# SCH_lic-555_2025-01-28.net
KiCad netlist of a schematic drawn in EasyEDA
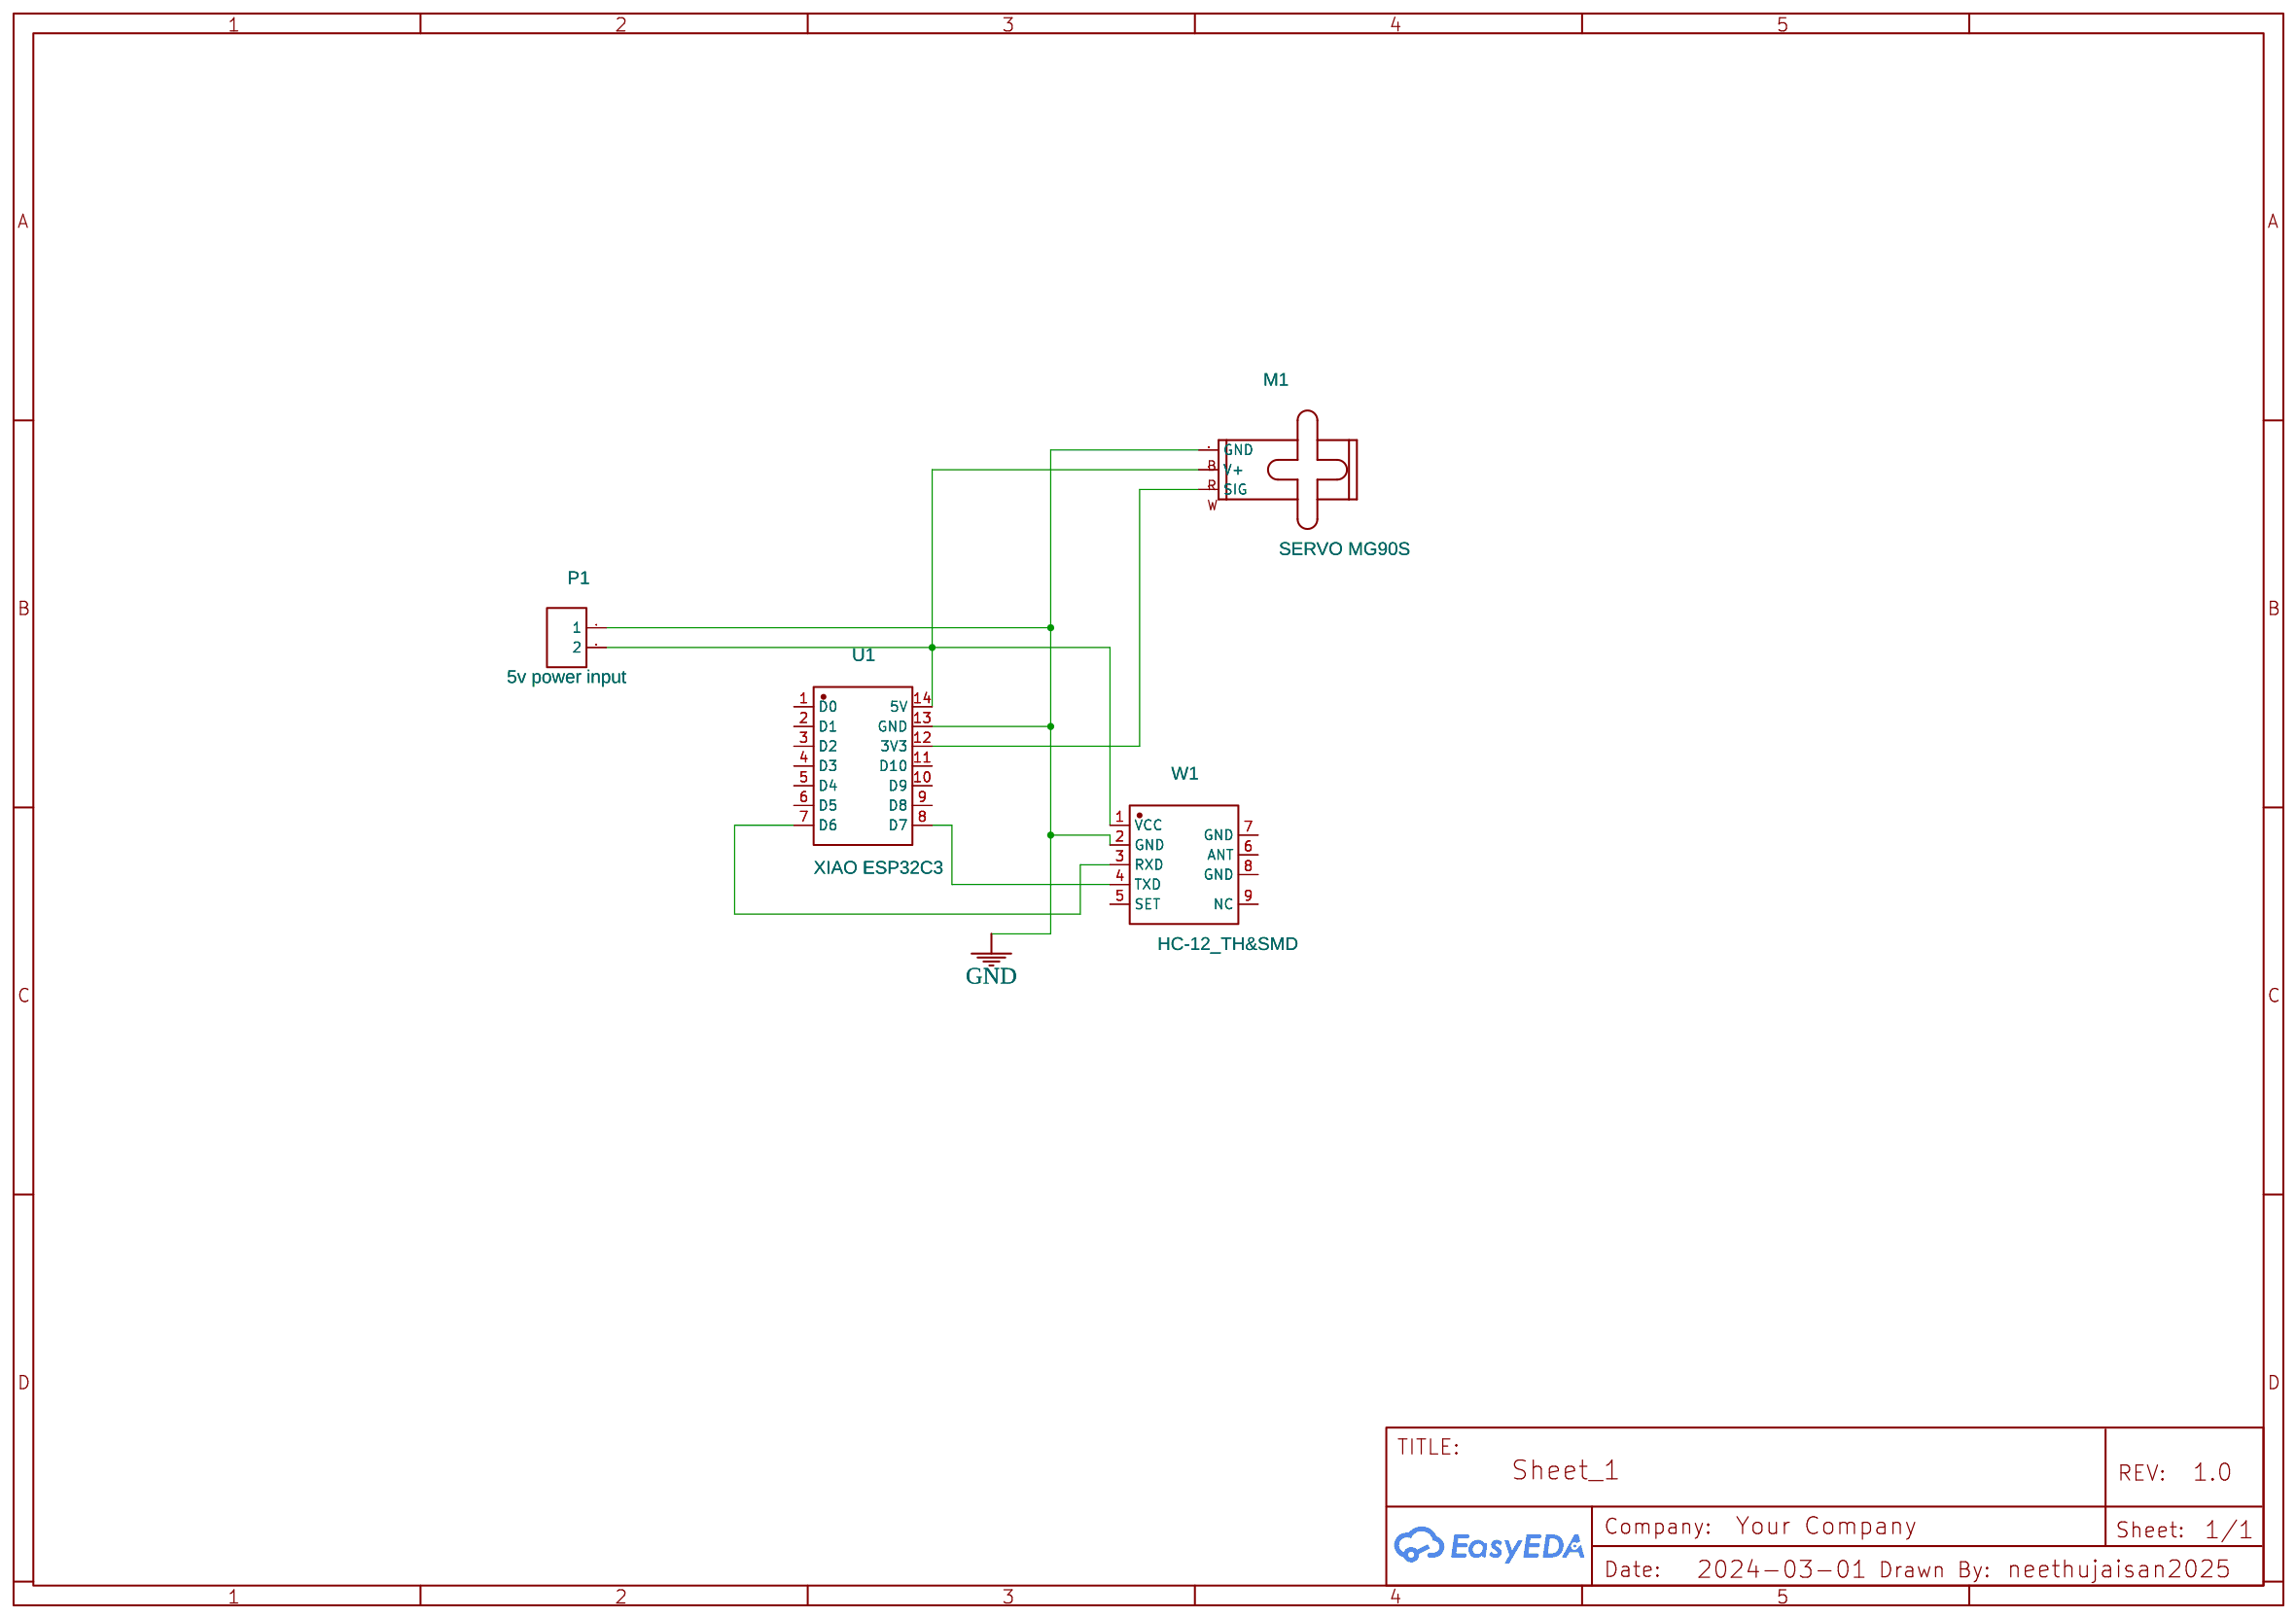
[diagram p0: schematic sheet]

(export (version "E")
  (design (tool "Eeschema 10.0.6"))
  (components
    (comp (ref "M1") (value "SERVO MG90S") (libsource (lib "") (part "SMALL_SERVO")))
    (comp (ref "P1") (value "5v power input") (libsource (lib "") (part "HDR-F-2.54_1x2")))
    (comp (ref "U1") (value "XIAO ESP32C3") (libsource (lib "") (part "XIAO ESP32C3")))
    (comp (ref "W1") (value "HC-12_TH&SMD") (libsource (lib "") (part "HC-12_TH&SMD")))
  )
  (nets
    (net (code "1") (name "GND") (class "Default")
      (node (ref "M1") (pin "3") (pinfunction "GND_3") (pintype "unspecified"))
      (node (ref "P1") (pin "1") (pinfunction "1_1") (pintype "input"))
      (node (ref "U1") (pin "13") (pinfunction "GND_13") (pintype "unspecified"))
      (node (ref "W1") (pin "2") (pinfunction "GND_2") (pintype "unspecified"))
    )
    (net (code "2") (name "Net-(M1-SIG)") (class "Default")
      (node (ref "M1") (pin "1") (pinfunction "SIG_1") (pintype "unspecified"))
      (node (ref "U1") (pin "12") (pinfunction "3V3_12") (pintype "unspecified"))
    )
    (net (code "3") (name "Net-(M1-V+)") (class "Default")
      (node (ref "M1") (pin "2") (pinfunction "V+_2") (pintype "unspecified"))
      (node (ref "P1") (pin "2") (pinfunction "2_2") (pintype "input"))
      (node (ref "U1") (pin "14") (pinfunction "5V_14") (pintype "unspecified"))
      (node (ref "W1") (pin "1") (pinfunction "VCC_1") (pintype "unspecified"))
    )
    (net (code "4") (name "Net-(U1-D6)") (class "Default")
      (node (ref "U1") (pin "7") (pinfunction "D6_7") (pintype "unspecified"))
      (node (ref "W1") (pin "3") (pinfunction "RXD_3") (pintype "unspecified"))
    )
    (net (code "5") (name "Net-(U1-D7)") (class "Default")
      (node (ref "U1") (pin "8") (pinfunction "D7_8") (pintype "unspecified"))
      (node (ref "W1") (pin "4") (pinfunction "TXD_4") (pintype "unspecified"))
    )
    (net (code "6") (name "unconnected-(U1-D0-Pad1)") (class "Default")
      (node (ref "U1") (pin "1") (pinfunction "D0_1") (pintype "unspecified"))
    )
    (net (code "7") (name "unconnected-(U1-D1-Pad2)") (class "Default")
      (node (ref "U1") (pin "2") (pinfunction "D1_2") (pintype "unspecified"))
    )
    (net (code "8") (name "unconnected-(U1-D2-Pad3)") (class "Default")
      (node (ref "U1") (pin "3") (pinfunction "D2_3") (pintype "unspecified"))
    )
    (net (code "9") (name "unconnected-(U1-D3-Pad4)") (class "Default")
      (node (ref "U1") (pin "4") (pinfunction "D3_4") (pintype "unspecified"))
    )
    (net (code "10") (name "unconnected-(U1-D4-Pad5)") (class "Default")
      (node (ref "U1") (pin "5") (pinfunction "D4_5") (pintype "unspecified"))
    )
    (net (code "11") (name "unconnected-(U1-D5-Pad6)") (class "Default")
      (node (ref "U1") (pin "6") (pinfunction "D5_6") (pintype "unspecified"))
    )
    (net (code "12") (name "unconnected-(U1-D8-Pad9)") (class "Default")
      (node (ref "U1") (pin "9") (pinfunction "D8_9") (pintype "unspecified"))
    )
    (net (code "13") (name "unconnected-(U1-D9-Pad10)") (class "Default")
      (node (ref "U1") (pin "10") (pinfunction "D9_10") (pintype "unspecified"))
    )
    (net (code "14") (name "unconnected-(U1-D10-Pad11)") (class "Default")
      (node (ref "U1") (pin "11") (pinfunction "D10_11") (pintype "unspecified"))
    )
    (net (code "15") (name "unconnected-(W1-ANT-Pad6)") (class "Default")
      (node (ref "W1") (pin "6") (pinfunction "ANT_6") (pintype "unspecified"))
    )
    (net (code "16") (name "unconnected-(W1-GND-Pad7)") (class "Default")
      (node (ref "W1") (pin "7") (pinfunction "GND_7") (pintype "unspecified"))
    )
    (net (code "17") (name "unconnected-(W1-GND-Pad8)") (class "Default")
      (node (ref "W1") (pin "8") (pinfunction "GND_8") (pintype "unspecified"))
    )
    (net (code "18") (name "unconnected-(W1-NC-Pad9)") (class "Default")
      (node (ref "W1") (pin "9") (pinfunction "NC_9") (pintype "unspecified"))
    )
    (net (code "19") (name "unconnected-(W1-SET-Pad5)") (class "Default")
      (node (ref "W1") (pin "5") (pinfunction "SET_5") (pintype "unspecified"))
    )
  )
)
